# NT0X67AA.net
KiCad netlist of a schematic drawn in EAGLE
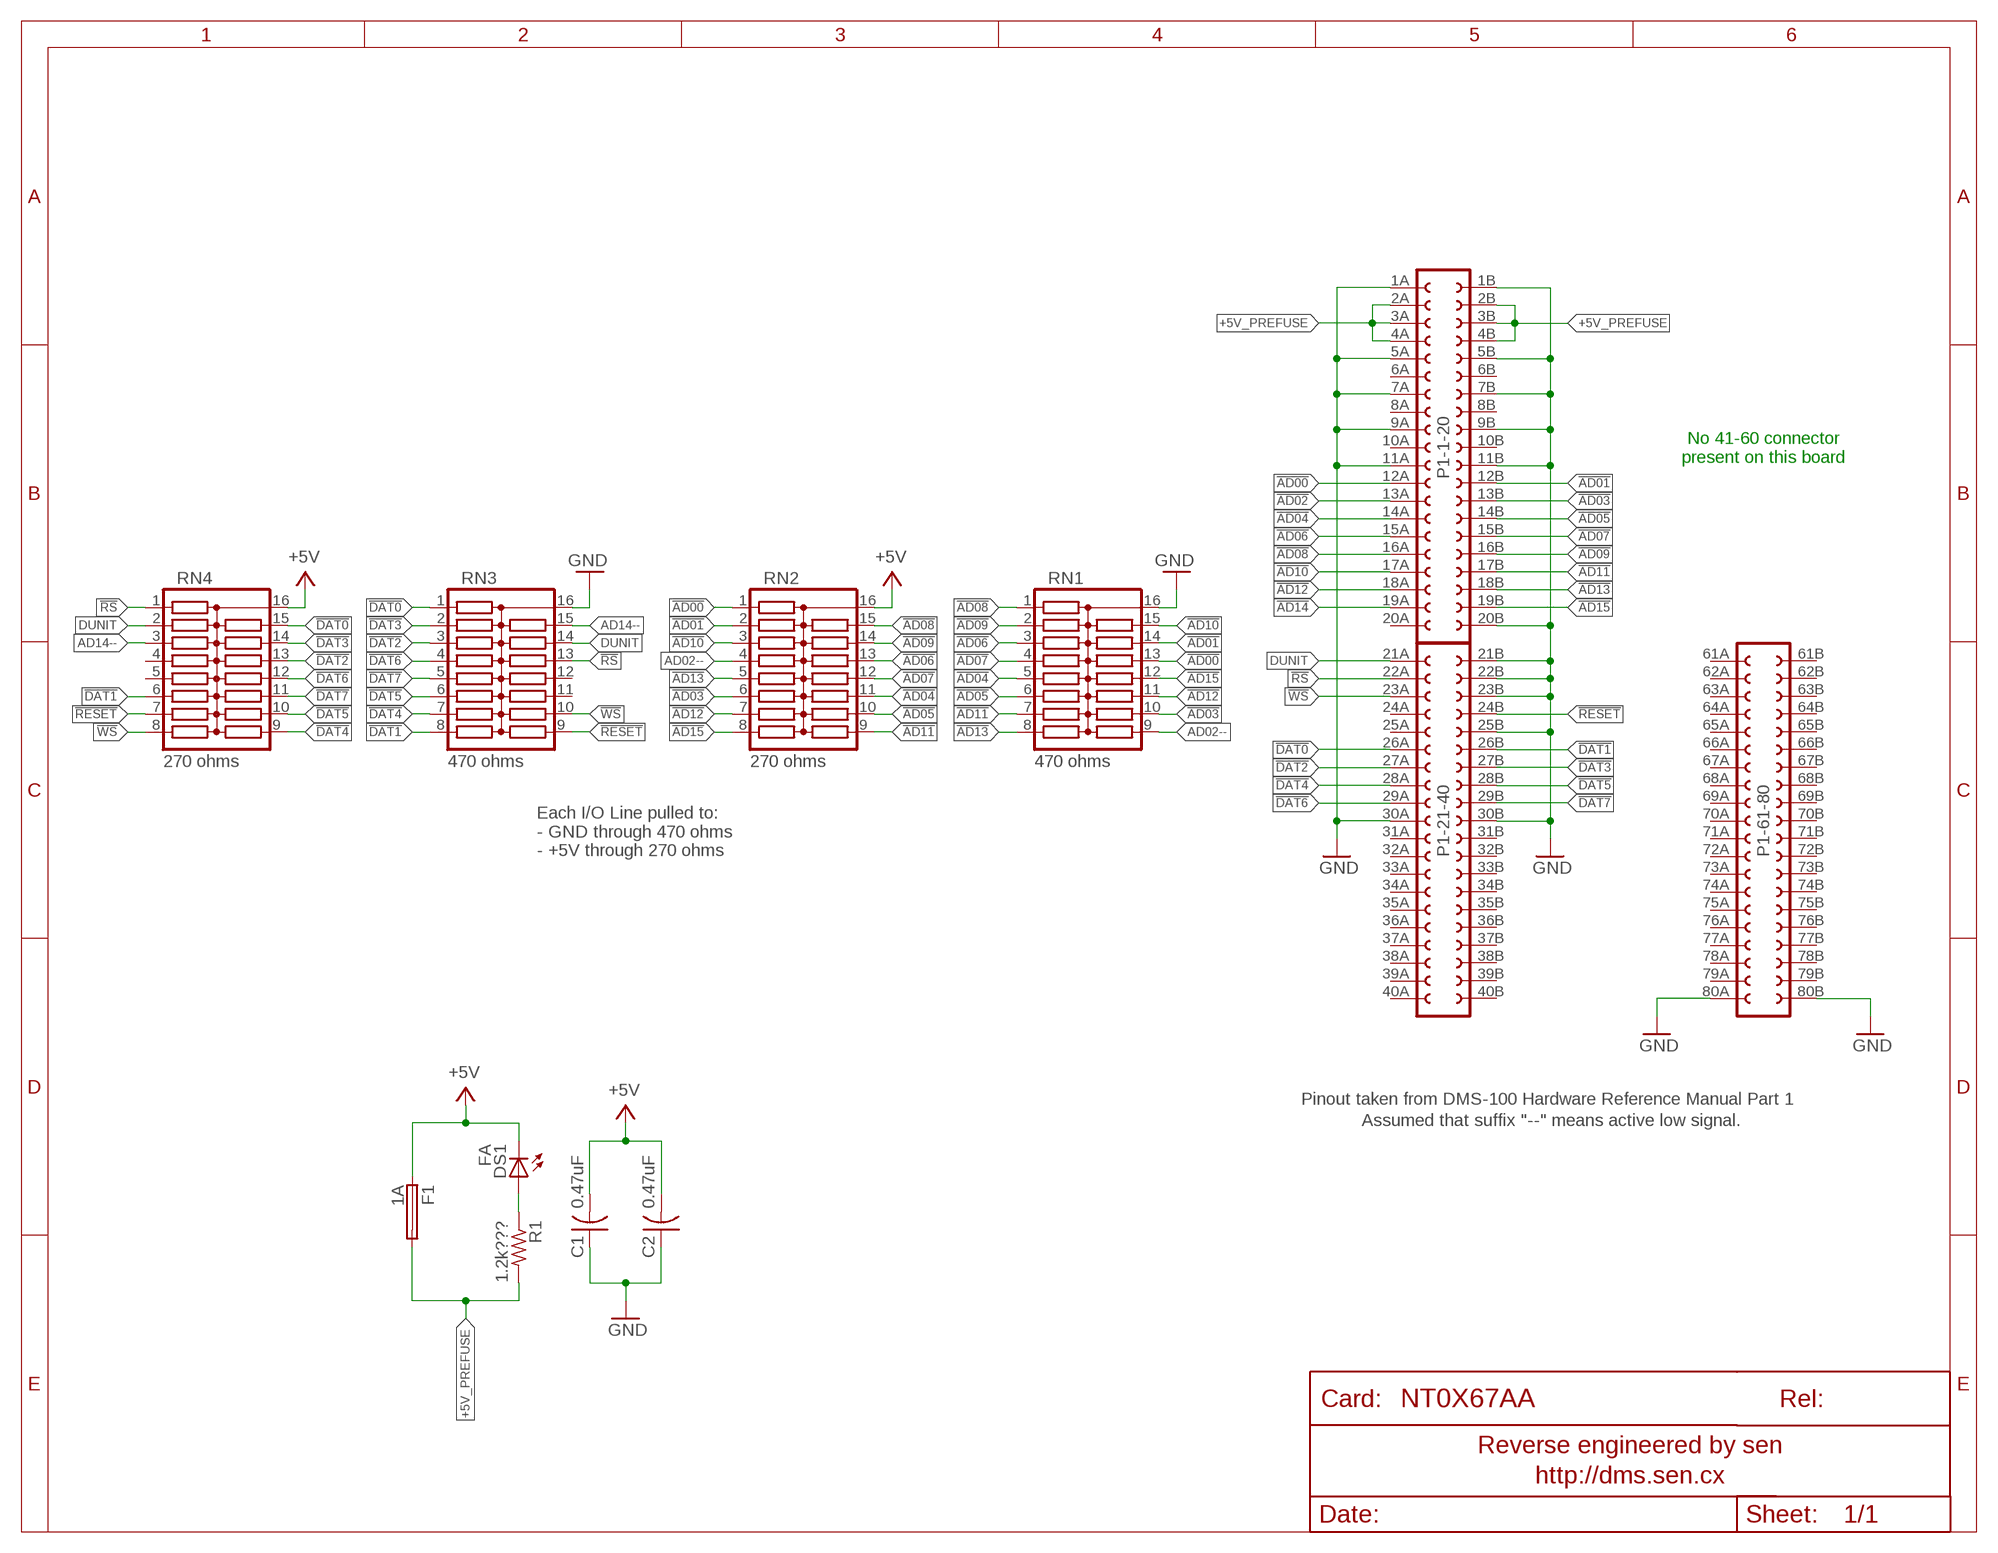
[diagram p0: schematic, sheet 1]

(export (version "E")
  (design (tool "Eeschema 10.0.6"))
  (components
    (comp (ref "C1")
      (value "0.47uF")
      (footprint "eagle-import:C150-054X183")
      (libsource (lib "eagle-import") (part "C-US150-054X183"))
    )
    (comp (ref "C2")
      (value "0.47uF")
      (footprint "eagle-import:C150-054X183")
      (libsource (lib "eagle-import") (part "C-US150-054X183"))
    )
    (comp (ref "DS1")
      (value "FA")
      (footprint "eagle-import:LED5MM")
      (libsource (lib "eagle-import") (part "LED5MM"))
    )
    (comp (ref "F1")
      (value "1A")
      (footprint "eagle-import:PICOFUSE")
      (libsource (lib "eagle-import") (part "FUSEPICOFUSE"))
    )
    (comp (ref "P1")
      (value "FE80-2W-HALFKEY")
      (footprint "eagle-import:FE80-2W-HALFKEY")
      (libsource (lib "eagle-import") (part "FE80-2W-HALFKEY"))
    )
    (comp (ref "R1")
      (value "1.2k???")
      (footprint "eagle-import:0207_15")
      (libsource (lib "eagle-import") (part "R-US_0207/15"))
    )
    (comp (ref "RN1")
      (value "470 ohms")
      (footprint "eagle-import:DIL16")
      (libsource (lib "eagle-import") (part "15R"))
    )
    (comp (ref "RN2")
      (value "270 ohms")
      (footprint "eagle-import:DIL16")
      (libsource (lib "eagle-import") (part "15R"))
    )
    (comp (ref "RN3")
      (value "470 ohms")
      (footprint "eagle-import:DIL16")
      (libsource (lib "eagle-import") (part "15R"))
    )
    (comp (ref "RN4")
      (value "270 ohms")
      (footprint "eagle-import:DIL16")
      (libsource (lib "eagle-import") (part "15R"))
    )
  )
  (nets
    (net (code "1") (name "+5V") (class "Default")
      (node (ref "C1") (pin "2") (pinfunction "2_2") (pintype "passive"))
      (node (ref "C2") (pin "2") (pinfunction "2_2") (pintype "passive"))
      (node (ref "DS1") (pin "K") (pinfunction "C_K") (pintype "passive"))
      (node (ref "F1") (pin "1") (pinfunction "1_1") (pintype "passive"))
      (node (ref "RN2") (pin "16") (pinfunction "16_16") (pintype "passive"))
      (node (ref "RN4") (pin "16") (pinfunction "16_16") (pintype "passive"))
    )
    (net (code "2") (name "+5V_PREFUSE") (class "Default")
      (node (ref "F1") (pin "2") (pinfunction "2_2") (pintype "passive"))
      (node (ref "P1") (pin "2A") (pinfunction "2A_2A") (pintype "passive"))
      (node (ref "P1") (pin "2B") (pinfunction "2B_2B") (pintype "passive"))
      (node (ref "P1") (pin "3A") (pinfunction "3A_3A") (pintype "passive"))
      (node (ref "P1") (pin "3B") (pinfunction "3B_3B") (pintype "passive"))
      (node (ref "P1") (pin "4A") (pinfunction "4A_4A") (pintype "passive"))
      (node (ref "P1") (pin "4B") (pinfunction "4B_4B") (pintype "passive"))
      (node (ref "R1") (pin "2") (pinfunction "2_2") (pintype "passive"))
    )
    (net (code "3") (name "/~{AD00}") (class "Default")
      (node (ref "P1") (pin "12A") (pinfunction "12A_12A") (pintype "passive"))
      (node (ref "RN1") (pin "13") (pinfunction "13_13") (pintype "passive"))
      (node (ref "RN2") (pin "1") (pinfunction "1_1") (pintype "passive"))
    )
    (net (code "4") (name "/~{AD01}") (class "Default")
      (node (ref "P1") (pin "12B") (pinfunction "12B_12B") (pintype "passive"))
      (node (ref "RN1") (pin "14") (pinfunction "14_14") (pintype "passive"))
      (node (ref "RN2") (pin "2") (pinfunction "2_2") (pintype "passive"))
    )
    (net (code "5") (name "/~{AD02}") (class "Default")
      (node (ref "P1") (pin "13A") (pinfunction "13A_13A") (pintype "passive"))
    )
    (net (code "6") (name "/~{AD03}") (class "Default")
      (node (ref "P1") (pin "13B") (pinfunction "13B_13B") (pintype "passive"))
      (node (ref "RN1") (pin "10") (pinfunction "10_10") (pintype "passive"))
      (node (ref "RN2") (pin "6") (pinfunction "6_6") (pintype "passive"))
    )
    (net (code "7") (name "/~{AD04}") (class "Default")
      (node (ref "P1") (pin "14A") (pinfunction "14A_14A") (pintype "passive"))
      (node (ref "RN1") (pin "5") (pinfunction "5_5") (pintype "passive"))
      (node (ref "RN2") (pin "11") (pinfunction "11_11") (pintype "passive"))
    )
    (net (code "8") (name "/~{AD05}") (class "Default")
      (node (ref "P1") (pin "14B") (pinfunction "14B_14B") (pintype "passive"))
      (node (ref "RN1") (pin "6") (pinfunction "6_6") (pintype "passive"))
      (node (ref "RN2") (pin "10") (pinfunction "10_10") (pintype "passive"))
    )
    (net (code "9") (name "/~{AD06}") (class "Default")
      (node (ref "P1") (pin "15A") (pinfunction "15A_15A") (pintype "passive"))
      (node (ref "RN1") (pin "3") (pinfunction "3_3") (pintype "passive"))
      (node (ref "RN2") (pin "13") (pinfunction "13_13") (pintype "passive"))
    )
    (net (code "10") (name "/~{AD07}") (class "Default")
      (node (ref "P1") (pin "15B") (pinfunction "15B_15B") (pintype "passive"))
      (node (ref "RN1") (pin "4") (pinfunction "4_4") (pintype "passive"))
      (node (ref "RN2") (pin "12") (pinfunction "12_12") (pintype "passive"))
    )
    (net (code "11") (name "/~{AD08}") (class "Default")
      (node (ref "P1") (pin "16A") (pinfunction "16A_16A") (pintype "passive"))
      (node (ref "RN1") (pin "1") (pinfunction "1_1") (pintype "passive"))
      (node (ref "RN2") (pin "15") (pinfunction "15_15") (pintype "passive"))
    )
    (net (code "12") (name "/~{AD09}") (class "Default")
      (node (ref "P1") (pin "16B") (pinfunction "16B_16B") (pintype "passive"))
      (node (ref "RN1") (pin "2") (pinfunction "2_2") (pintype "passive"))
      (node (ref "RN2") (pin "14") (pinfunction "14_14") (pintype "passive"))
    )
    (net (code "13") (name "/~{AD10}") (class "Default")
      (node (ref "P1") (pin "17A") (pinfunction "17A_17A") (pintype "passive"))
      (node (ref "RN1") (pin "15") (pinfunction "15_15") (pintype "passive"))
      (node (ref "RN2") (pin "3") (pinfunction "3_3") (pintype "passive"))
    )
    (net (code "14") (name "/~{AD11}") (class "Default")
      (node (ref "P1") (pin "17B") (pinfunction "17B_17B") (pintype "passive"))
      (node (ref "RN1") (pin "7") (pinfunction "7_7") (pintype "passive"))
      (node (ref "RN2") (pin "9") (pinfunction "9_9") (pintype "passive"))
    )
    (net (code "15") (name "/~{AD12}") (class "Default")
      (node (ref "P1") (pin "18A") (pinfunction "18A_18A") (pintype "passive"))
      (node (ref "RN1") (pin "11") (pinfunction "11_11") (pintype "passive"))
      (node (ref "RN2") (pin "7") (pinfunction "7_7") (pintype "passive"))
    )
    (net (code "16") (name "/~{AD13}") (class "Default")
      (node (ref "P1") (pin "18B") (pinfunction "18B_18B") (pintype "passive"))
      (node (ref "RN1") (pin "8") (pinfunction "8_8") (pintype "passive"))
      (node (ref "RN2") (pin "5") (pinfunction "5_5") (pintype "passive"))
    )
    (net (code "17") (name "/~{AD14}") (class "Default")
      (node (ref "P1") (pin "19A") (pinfunction "19A_19A") (pintype "passive"))
    )
    (net (code "18") (name "/~{AD15}") (class "Default")
      (node (ref "P1") (pin "19B") (pinfunction "19B_19B") (pintype "passive"))
      (node (ref "RN1") (pin "12") (pinfunction "12_12") (pintype "passive"))
      (node (ref "RN2") (pin "8") (pinfunction "8_8") (pintype "passive"))
    )
    (net (code "19") (name "/~{DAT0}") (class "Default")
      (node (ref "P1") (pin "26A") (pinfunction "6A_26A") (pintype "passive"))
      (node (ref "RN3") (pin "1") (pinfunction "1_1") (pintype "passive"))
      (node (ref "RN4") (pin "15") (pinfunction "15_15") (pintype "passive"))
    )
    (net (code "20") (name "/~{DAT1}") (class "Default")
      (node (ref "P1") (pin "26B") (pinfunction "6B_26B") (pintype "passive"))
      (node (ref "RN3") (pin "8") (pinfunction "8_8") (pintype "passive"))
      (node (ref "RN4") (pin "6") (pinfunction "6_6") (pintype "passive"))
    )
    (net (code "21") (name "/~{DAT2}") (class "Default")
      (node (ref "P1") (pin "27A") (pinfunction "7A_27A") (pintype "passive"))
      (node (ref "RN3") (pin "3") (pinfunction "3_3") (pintype "passive"))
      (node (ref "RN4") (pin "13") (pinfunction "13_13") (pintype "passive"))
    )
    (net (code "22") (name "/~{DAT3}") (class "Default")
      (node (ref "P1") (pin "27B") (pinfunction "7B_27B") (pintype "passive"))
      (node (ref "RN3") (pin "2") (pinfunction "2_2") (pintype "passive"))
      (node (ref "RN4") (pin "14") (pinfunction "14_14") (pintype "passive"))
    )
    (net (code "23") (name "/~{DAT4}") (class "Default")
      (node (ref "P1") (pin "28A") (pinfunction "8A_28A") (pintype "passive"))
      (node (ref "RN3") (pin "7") (pinfunction "7_7") (pintype "passive"))
      (node (ref "RN4") (pin "9") (pinfunction "9_9") (pintype "passive"))
    )
    (net (code "24") (name "/~{DAT5}") (class "Default")
      (node (ref "P1") (pin "28B") (pinfunction "8B_28B") (pintype "passive"))
      (node (ref "RN3") (pin "6") (pinfunction "6_6") (pintype "passive"))
      (node (ref "RN4") (pin "10") (pinfunction "10_10") (pintype "passive"))
    )
    (net (code "25") (name "/~{DAT6}") (class "Default")
      (node (ref "P1") (pin "29A") (pinfunction "9A_29A") (pintype "passive"))
      (node (ref "RN3") (pin "4") (pinfunction "4_4") (pintype "passive"))
      (node (ref "RN4") (pin "12") (pinfunction "12_12") (pintype "passive"))
    )
    (net (code "26") (name "/~{DAT7}") (class "Default")
      (node (ref "P1") (pin "29B") (pinfunction "9B_29B") (pintype "passive"))
      (node (ref "RN3") (pin "5") (pinfunction "5_5") (pintype "passive"))
      (node (ref "RN4") (pin "11") (pinfunction "11_11") (pintype "passive"))
    )
    (net (code "27") (name "/~{RESET}") (class "Default")
      (node (ref "P1") (pin "24B") (pinfunction "4B_24B") (pintype "passive"))
      (node (ref "RN3") (pin "9") (pinfunction "9_9") (pintype "passive"))
      (node (ref "RN4") (pin "7") (pinfunction "7_7") (pintype "passive"))
    )
    (net (code "28") (name "/~{RS}") (class "Default")
      (node (ref "P1") (pin "22A") (pinfunction "2A_22A") (pintype "passive"))
      (node (ref "RN3") (pin "13") (pinfunction "13_13") (pintype "passive"))
      (node (ref "RN4") (pin "1") (pinfunction "1_1") (pintype "passive"))
    )
    (net (code "29") (name "/~{WS}") (class "Default")
      (node (ref "P1") (pin "23A") (pinfunction "3A_23A") (pintype "passive"))
      (node (ref "RN3") (pin "10") (pinfunction "10_10") (pintype "passive"))
      (node (ref "RN4") (pin "8") (pinfunction "8_8") (pintype "passive"))
    )
    (net (code "30") (name "AD02--") (class "Default")
      (node (ref "RN1") (pin "9") (pinfunction "9_9") (pintype "passive"))
      (node (ref "RN2") (pin "4") (pinfunction "4_4") (pintype "passive"))
    )
    (net (code "31") (name "AD14--") (class "Default")
      (node (ref "RN3") (pin "15") (pinfunction "15_15") (pintype "passive"))
      (node (ref "RN4") (pin "3") (pinfunction "3_3") (pintype "passive"))
    )
    (net (code "32") (name "DUNIT") (class "Default")
      (node (ref "P1") (pin "21A") (pinfunction "1A_21A") (pintype "passive"))
      (node (ref "RN3") (pin "14") (pinfunction "14_14") (pintype "passive"))
      (node (ref "RN4") (pin "2") (pinfunction "2_2") (pintype "passive"))
    )
    (net (code "33") (name "GND") (class "Default")
      (node (ref "C1") (pin "1") (pinfunction "1_1") (pintype "passive"))
      (node (ref "C2") (pin "1") (pinfunction "1_1") (pintype "passive"))
      (node (ref "P1") (pin "11A") (pinfunction "11A_11A") (pintype "passive"))
      (node (ref "P1") (pin "11B") (pinfunction "11B_11B") (pintype "passive"))
      (node (ref "P1") (pin "1A") (pinfunction "1A_1A") (pintype "passive"))
      (node (ref "P1") (pin "1B") (pinfunction "1B_1B") (pintype "passive"))
      (node (ref "P1") (pin "20B") (pinfunction "20B_20B") (pintype "passive"))
      (node (ref "P1") (pin "21B") (pinfunction "1B_21B") (pintype "passive"))
      (node (ref "P1") (pin "22B") (pinfunction "2B_22B") (pintype "passive"))
      (node (ref "P1") (pin "23B") (pinfunction "3B_23B") (pintype "passive"))
      (node (ref "P1") (pin "25B") (pinfunction "5B_25B") (pintype "passive"))
      (node (ref "P1") (pin "30A") (pinfunction "10A_30A") (pintype "passive"))
      (node (ref "P1") (pin "30B") (pinfunction "10B_30B") (pintype "passive"))
      (node (ref "P1") (pin "5A") (pinfunction "5A_5A") (pintype "passive"))
      (node (ref "P1") (pin "5B") (pinfunction "5B_5B") (pintype "passive"))
      (node (ref "P1") (pin "7A") (pinfunction "7A_7A") (pintype "passive"))
      (node (ref "P1") (pin "7B") (pinfunction "7B_7B") (pintype "passive"))
      (node (ref "P1") (pin "80A") (pinfunction "20A_80A") (pintype "passive"))
      (node (ref "P1") (pin "80B") (pinfunction "20B_80B") (pintype "passive"))
      (node (ref "P1") (pin "9A") (pinfunction "9A_9A") (pintype "passive"))
      (node (ref "P1") (pin "9B") (pinfunction "9B_9B") (pintype "passive"))
      (node (ref "RN1") (pin "16") (pinfunction "16_16") (pintype "passive"))
      (node (ref "RN3") (pin "16") (pinfunction "16_16") (pintype "passive"))
    )
    (net (code "34") (name "Net-(DS1-PadA)") (class "Default")
      (node (ref "DS1") (pin "A") (pinfunction "A_A") (pintype "passive"))
      (node (ref "R1") (pin "1") (pinfunction "1_1") (pintype "passive"))
    )
    (net (code "35") (name "unconnected-(P1-Pad6A)") (class "Default")
      (node (ref "P1") (pin "6A") (pinfunction "6A_6A") (pintype "passive"))
    )
    (net (code "36") (name "unconnected-(P1-Pad6B)") (class "Default")
      (node (ref "P1") (pin "6B") (pinfunction "6B_6B") (pintype "passive"))
    )
    (net (code "37") (name "unconnected-(P1-Pad8A)") (class "Default")
      (node (ref "P1") (pin "8A") (pinfunction "8A_8A") (pintype "passive"))
    )
    (net (code "38") (name "unconnected-(P1-Pad8B)") (class "Default")
      (node (ref "P1") (pin "8B") (pinfunction "8B_8B") (pintype "passive"))
    )
    (net (code "39") (name "unconnected-(P1-Pad10A)") (class "Default")
      (node (ref "P1") (pin "10A") (pinfunction "10A_10A") (pintype "passive"))
    )
    (net (code "40") (name "unconnected-(P1-Pad10B)") (class "Default")
      (node (ref "P1") (pin "10B") (pinfunction "10B_10B") (pintype "passive"))
    )
    (net (code "41") (name "unconnected-(P1-Pad20A)") (class "Default")
      (node (ref "P1") (pin "20A") (pinfunction "20A_20A") (pintype "passive"))
    )
    (net (code "42") (name "unconnected-(P1B-4A-Pad24A)") (class "Default")
      (node (ref "P1") (pin "24A") (pinfunction "4A_24A") (pintype "passive"))
    )
    (net (code "43") (name "unconnected-(P1B-5A-Pad25A)") (class "Default")
      (node (ref "P1") (pin "25A") (pinfunction "5A_25A") (pintype "passive"))
    )
    (net (code "44") (name "unconnected-(P1B-11A-Pad31A)") (class "Default")
      (node (ref "P1") (pin "31A") (pinfunction "11A_31A") (pintype "passive"))
    )
    (net (code "45") (name "unconnected-(P1B-11B-Pad31B)") (class "Default")
      (node (ref "P1") (pin "31B") (pinfunction "11B_31B") (pintype "passive"))
    )
    (net (code "46") (name "unconnected-(P1B-12A-Pad32A)") (class "Default")
      (node (ref "P1") (pin "32A") (pinfunction "12A_32A") (pintype "passive"))
    )
    (net (code "47") (name "unconnected-(P1B-12B-Pad32B)") (class "Default")
      (node (ref "P1") (pin "32B") (pinfunction "12B_32B") (pintype "passive"))
    )
    (net (code "48") (name "unconnected-(P1B-13A-Pad33A)") (class "Default")
      (node (ref "P1") (pin "33A") (pinfunction "13A_33A") (pintype "passive"))
    )
    (net (code "49") (name "unconnected-(P1B-13B-Pad33B)") (class "Default")
      (node (ref "P1") (pin "33B") (pinfunction "13B_33B") (pintype "passive"))
    )
    (net (code "50") (name "unconnected-(P1B-14A-Pad34A)") (class "Default")
      (node (ref "P1") (pin "34A") (pinfunction "14A_34A") (pintype "passive"))
    )
    (net (code "51") (name "unconnected-(P1B-14B-Pad34B)") (class "Default")
      (node (ref "P1") (pin "34B") (pinfunction "14B_34B") (pintype "passive"))
    )
    (net (code "52") (name "unconnected-(P1B-15A-Pad35A)") (class "Default")
      (node (ref "P1") (pin "35A") (pinfunction "15A_35A") (pintype "passive"))
    )
    (net (code "53") (name "unconnected-(P1B-15B-Pad35B)") (class "Default")
      (node (ref "P1") (pin "35B") (pinfunction "15B_35B") (pintype "passive"))
    )
    (net (code "54") (name "unconnected-(P1B-16A-Pad36A)") (class "Default")
      (node (ref "P1") (pin "36A") (pinfunction "16A_36A") (pintype "passive"))
    )
    (net (code "55") (name "unconnected-(P1B-16B-Pad36B)") (class "Default")
      (node (ref "P1") (pin "36B") (pinfunction "16B_36B") (pintype "passive"))
    )
    (net (code "56") (name "unconnected-(P1B-17A-Pad37A)") (class "Default")
      (node (ref "P1") (pin "37A") (pinfunction "17A_37A") (pintype "passive"))
    )
    (net (code "57") (name "unconnected-(P1B-17B-Pad37B)") (class "Default")
      (node (ref "P1") (pin "37B") (pinfunction "17B_37B") (pintype "passive"))
    )
    (net (code "58") (name "unconnected-(P1B-18A-Pad38A)") (class "Default")
      (node (ref "P1") (pin "38A") (pinfunction "18A_38A") (pintype "passive"))
    )
    (net (code "59") (name "unconnected-(P1B-18B-Pad38B)") (class "Default")
      (node (ref "P1") (pin "38B") (pinfunction "18B_38B") (pintype "passive"))
    )
    (net (code "60") (name "unconnected-(P1B-19A-Pad39A)") (class "Default")
      (node (ref "P1") (pin "39A") (pinfunction "19A_39A") (pintype "passive"))
    )
    (net (code "61") (name "unconnected-(P1B-19B-Pad39B)") (class "Default")
      (node (ref "P1") (pin "39B") (pinfunction "19B_39B") (pintype "passive"))
    )
    (net (code "62") (name "unconnected-(P1B-20A-Pad40A)") (class "Default")
      (node (ref "P1") (pin "40A") (pinfunction "20A_40A") (pintype "passive"))
    )
    (net (code "63") (name "unconnected-(P1B-20B-Pad40B)") (class "Default")
      (node (ref "P1") (pin "40B") (pinfunction "20B_40B") (pintype "passive"))
    )
    (net (code "64") (name "unconnected-(P1D-1A-Pad61A)") (class "Default")
      (node (ref "P1") (pin "61A") (pinfunction "1A_61A") (pintype "passive"))
    )
    (net (code "65") (name "unconnected-(P1D-1B-Pad61B)") (class "Default")
      (node (ref "P1") (pin "61B") (pinfunction "1B_61B") (pintype "passive"))
    )
    (net (code "66") (name "unconnected-(P1D-2A-Pad62A)") (class "Default")
      (node (ref "P1") (pin "62A") (pinfunction "2A_62A") (pintype "passive"))
    )
    (net (code "67") (name "unconnected-(P1D-2B-Pad62B)") (class "Default")
      (node (ref "P1") (pin "62B") (pinfunction "2B_62B") (pintype "passive"))
    )
    (net (code "68") (name "unconnected-(P1D-3A-Pad63A)") (class "Default")
      (node (ref "P1") (pin "63A") (pinfunction "3A_63A") (pintype "passive"))
    )
    (net (code "69") (name "unconnected-(P1D-3B-Pad63B)") (class "Default")
      (node (ref "P1") (pin "63B") (pinfunction "3B_63B") (pintype "passive"))
    )
    (net (code "70") (name "unconnected-(P1D-4A-Pad64A)") (class "Default")
      (node (ref "P1") (pin "64A") (pinfunction "4A_64A") (pintype "passive"))
    )
    (net (code "71") (name "unconnected-(P1D-4B-Pad64B)") (class "Default")
      (node (ref "P1") (pin "64B") (pinfunction "4B_64B") (pintype "passive"))
    )
    (net (code "72") (name "unconnected-(P1D-5A-Pad65A)") (class "Default")
      (node (ref "P1") (pin "65A") (pinfunction "5A_65A") (pintype "passive"))
    )
    (net (code "73") (name "unconnected-(P1D-5B-Pad65B)") (class "Default")
      (node (ref "P1") (pin "65B") (pinfunction "5B_65B") (pintype "passive"))
    )
    (net (code "74") (name "unconnected-(P1D-6A-Pad66A)") (class "Default")
      (node (ref "P1") (pin "66A") (pinfunction "6A_66A") (pintype "passive"))
    )
    (net (code "75") (name "unconnected-(P1D-6B-Pad66B)") (class "Default")
      (node (ref "P1") (pin "66B") (pinfunction "6B_66B") (pintype "passive"))
    )
    (net (code "76") (name "unconnected-(P1D-7A-Pad67A)") (class "Default")
      (node (ref "P1") (pin "67A") (pinfunction "7A_67A") (pintype "passive"))
    )
    (net (code "77") (name "unconnected-(P1D-7B-Pad67B)") (class "Default")
      (node (ref "P1") (pin "67B") (pinfunction "7B_67B") (pintype "passive"))
    )
    (net (code "78") (name "unconnected-(P1D-8A-Pad68A)") (class "Default")
      (node (ref "P1") (pin "68A") (pinfunction "8A_68A") (pintype "passive"))
    )
    (net (code "79") (name "unconnected-(P1D-8B-Pad68B)") (class "Default")
      (node (ref "P1") (pin "68B") (pinfunction "8B_68B") (pintype "passive"))
    )
    (net (code "80") (name "unconnected-(P1D-9A-Pad69A)") (class "Default")
      (node (ref "P1") (pin "69A") (pinfunction "9A_69A") (pintype "passive"))
    )
    (net (code "81") (name "unconnected-(P1D-9B-Pad69B)") (class "Default")
      (node (ref "P1") (pin "69B") (pinfunction "9B_69B") (pintype "passive"))
    )
    (net (code "82") (name "unconnected-(P1D-10A-Pad70A)") (class "Default")
      (node (ref "P1") (pin "70A") (pinfunction "10A_70A") (pintype "passive"))
    )
    (net (code "83") (name "unconnected-(P1D-10B-Pad70B)") (class "Default")
      (node (ref "P1") (pin "70B") (pinfunction "10B_70B") (pintype "passive"))
    )
    (net (code "84") (name "unconnected-(P1D-11A-Pad71A)") (class "Default")
      (node (ref "P1") (pin "71A") (pinfunction "11A_71A") (pintype "passive"))
    )
    (net (code "85") (name "unconnected-(P1D-11B-Pad71B)") (class "Default")
      (node (ref "P1") (pin "71B") (pinfunction "11B_71B") (pintype "passive"))
    )
    (net (code "86") (name "unconnected-(P1D-12A-Pad72A)") (class "Default")
      (node (ref "P1") (pin "72A") (pinfunction "12A_72A") (pintype "passive"))
    )
    (net (code "87") (name "unconnected-(P1D-12B-Pad72B)") (class "Default")
      (node (ref "P1") (pin "72B") (pinfunction "12B_72B") (pintype "passive"))
    )
    (net (code "88") (name "unconnected-(P1D-13A-Pad73A)") (class "Default")
      (node (ref "P1") (pin "73A") (pinfunction "13A_73A") (pintype "passive"))
    )
    (net (code "89") (name "unconnected-(P1D-13B-Pad73B)") (class "Default")
      (node (ref "P1") (pin "73B") (pinfunction "13B_73B") (pintype "passive"))
    )
    (net (code "90") (name "unconnected-(P1D-14A-Pad74A)") (class "Default")
      (node (ref "P1") (pin "74A") (pinfunction "14A_74A") (pintype "passive"))
    )
    (net (code "91") (name "unconnected-(P1D-14B-Pad74B)") (class "Default")
      (node (ref "P1") (pin "74B") (pinfunction "14B_74B") (pintype "passive"))
    )
    (net (code "92") (name "unconnected-(P1D-15A-Pad75A)") (class "Default")
      (node (ref "P1") (pin "75A") (pinfunction "15A_75A") (pintype "passive"))
    )
    (net (code "93") (name "unconnected-(P1D-15B-Pad75B)") (class "Default")
      (node (ref "P1") (pin "75B") (pinfunction "15B_75B") (pintype "passive"))
    )
    (net (code "94") (name "unconnected-(P1D-16A-Pad76A)") (class "Default")
      (node (ref "P1") (pin "76A") (pinfunction "16A_76A") (pintype "passive"))
    )
    (net (code "95") (name "unconnected-(P1D-16B-Pad76B)") (class "Default")
      (node (ref "P1") (pin "76B") (pinfunction "16B_76B") (pintype "passive"))
    )
    (net (code "96") (name "unconnected-(P1D-17A-Pad77A)") (class "Default")
      (node (ref "P1") (pin "77A") (pinfunction "17A_77A") (pintype "passive"))
    )
    (net (code "97") (name "unconnected-(P1D-17B-Pad77B)") (class "Default")
      (node (ref "P1") (pin "77B") (pinfunction "17B_77B") (pintype "passive"))
    )
    (net (code "98") (name "unconnected-(P1D-18A-Pad78A)") (class "Default")
      (node (ref "P1") (pin "78A") (pinfunction "18A_78A") (pintype "passive"))
    )
    (net (code "99") (name "unconnected-(P1D-18B-Pad78B)") (class "Default")
      (node (ref "P1") (pin "78B") (pinfunction "18B_78B") (pintype "passive"))
    )
    (net (code "100") (name "unconnected-(P1D-19A-Pad79A)") (class "Default")
      (node (ref "P1") (pin "79A") (pinfunction "19A_79A") (pintype "passive"))
    )
    (net (code "101") (name "unconnected-(P1D-19B-Pad79B)") (class "Default")
      (node (ref "P1") (pin "79B") (pinfunction "19B_79B") (pintype "passive"))
    )
    (net (code "102") (name "unconnected-(RN3-Pad11)") (class "Default")
      (node (ref "RN3") (pin "11") (pinfunction "11_11") (pintype "passive"))
    )
    (net (code "103") (name "unconnected-(RN3-Pad12)") (class "Default")
      (node (ref "RN3") (pin "12") (pinfunction "12_12") (pintype "passive"))
    )
    (net (code "104") (name "unconnected-(RN4-Pad4)") (class "Default")
      (node (ref "RN4") (pin "4") (pinfunction "4_4") (pintype "passive"))
    )
    (net (code "105") (name "unconnected-(RN4-Pad5)") (class "Default")
      (node (ref "RN4") (pin "5") (pinfunction "5_5") (pintype "passive"))
    )
  )
)
